# Un_Bus_B.net
KiCad netlist of a schematic drawn in EAGLE
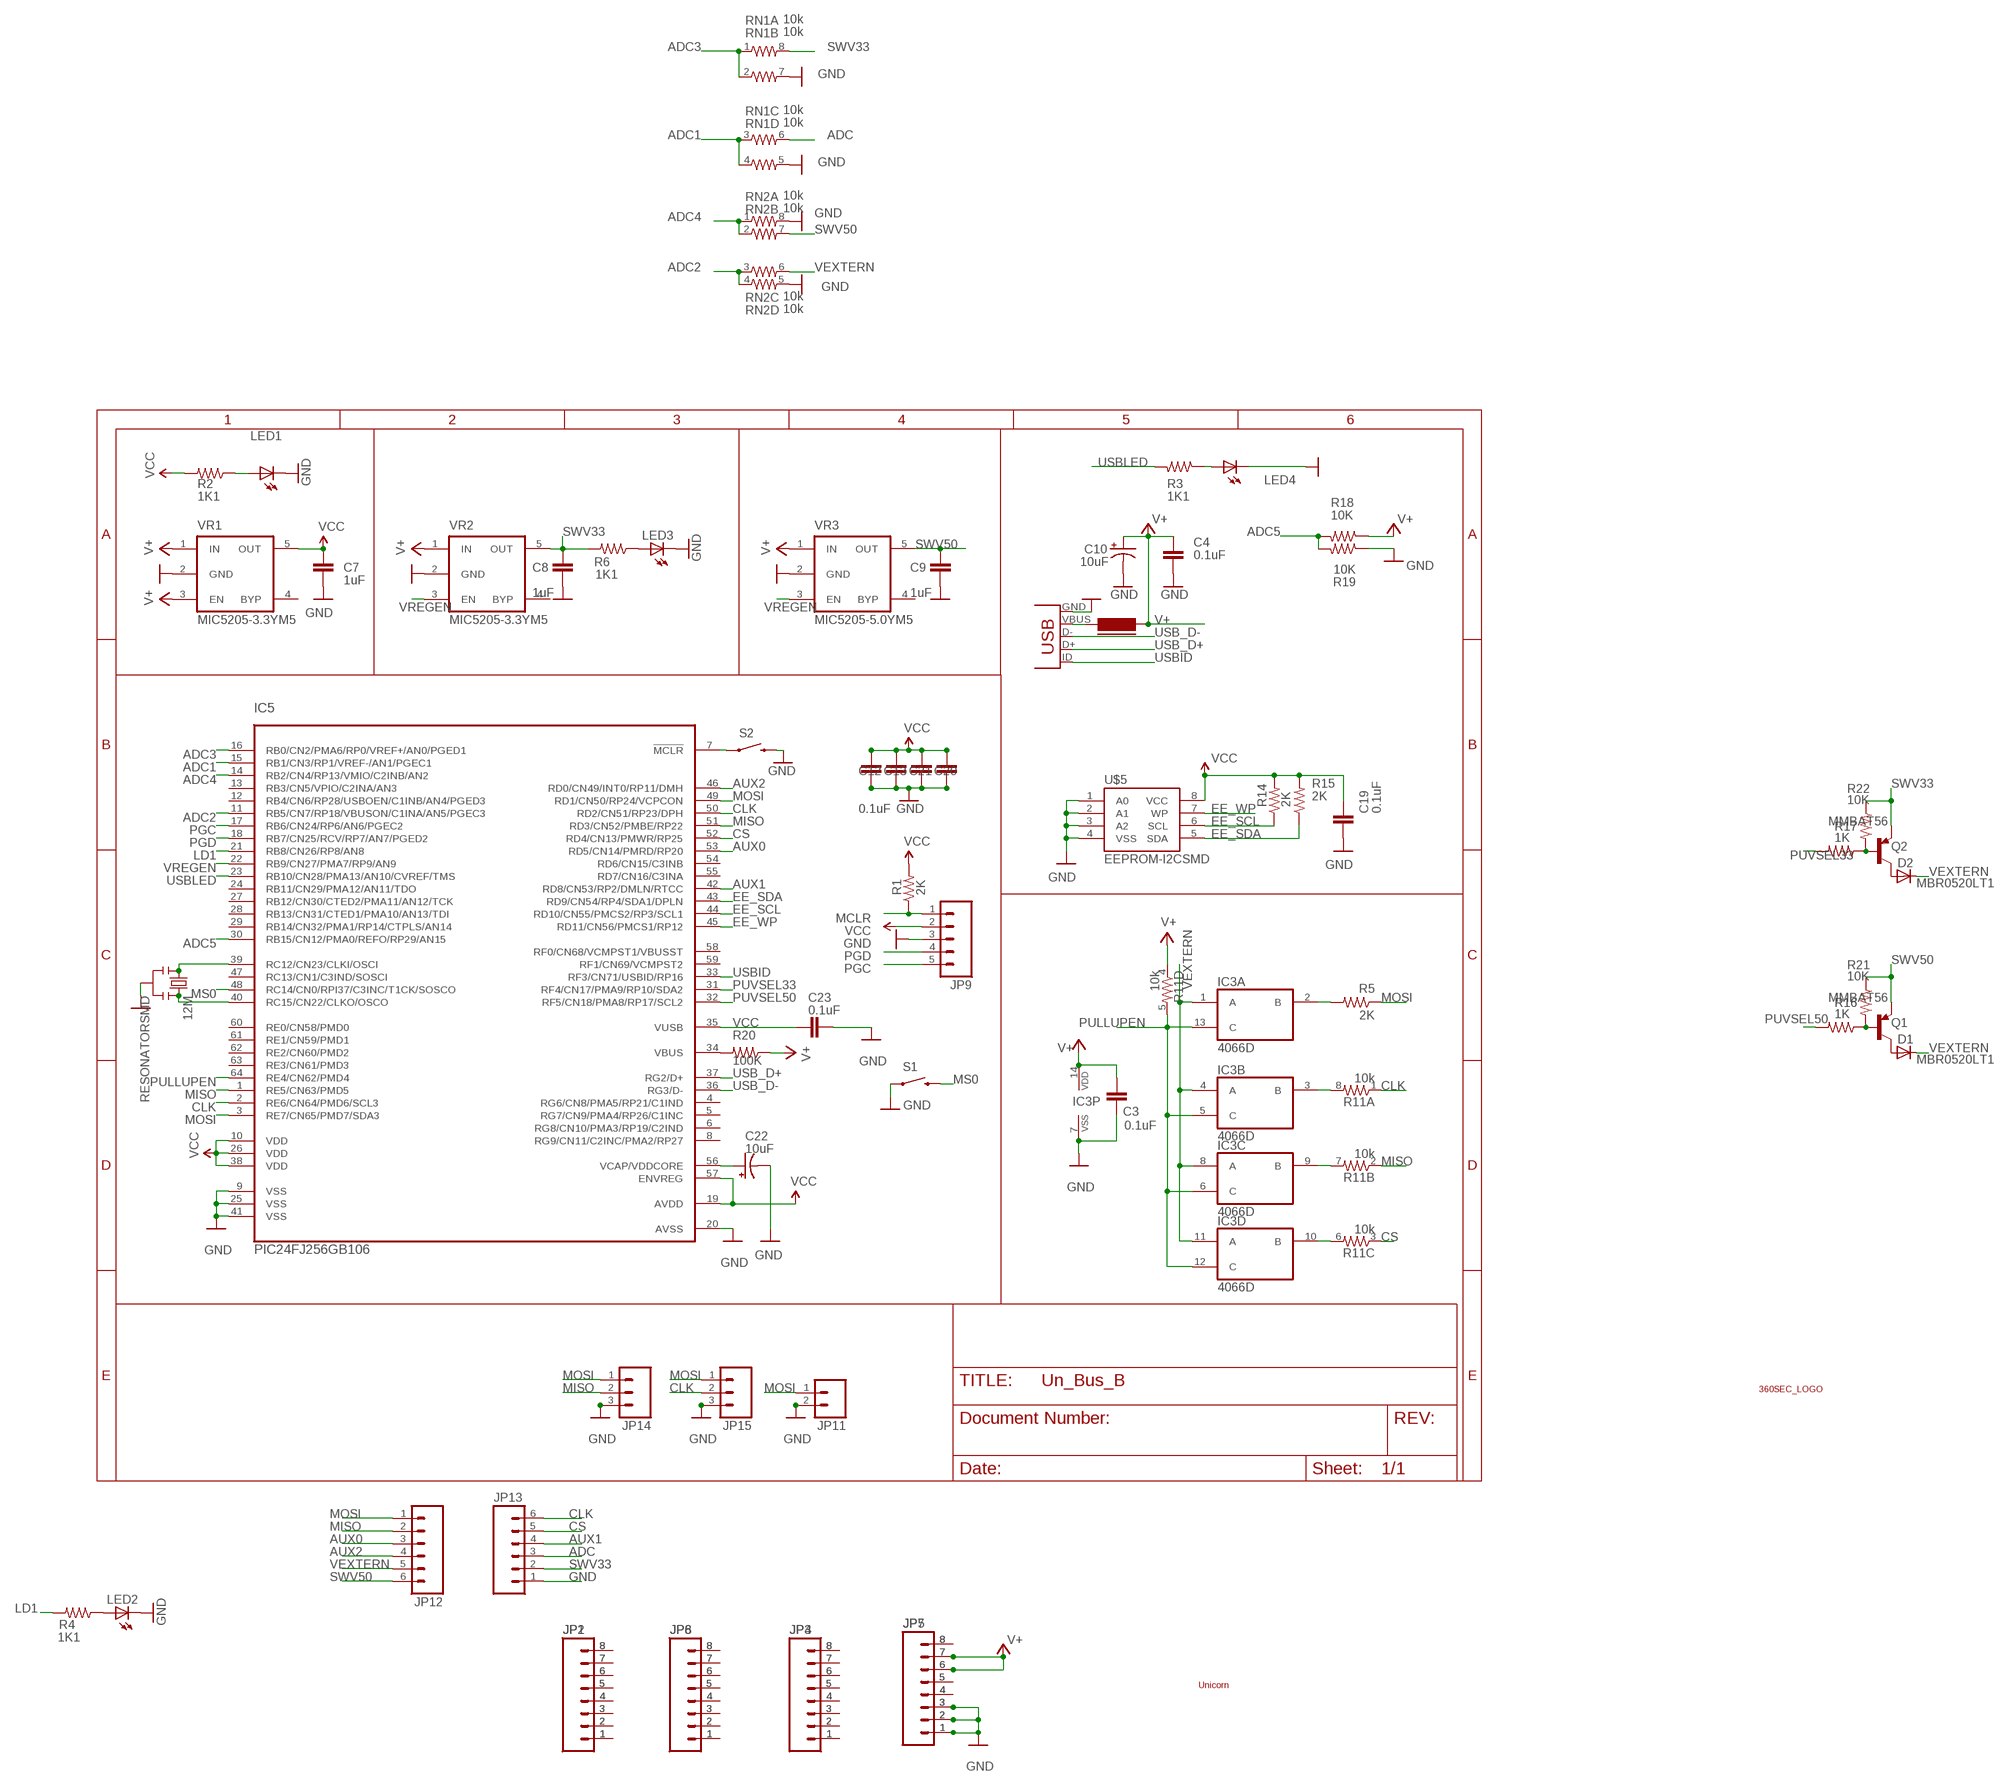
[diagram p0: schematic, sheet 1]

(export (version "E")
  (design (tool "Eeschema 10.0.6"))
  (components
    (comp (ref "12M")
      (value "RESONATORSMD")
      (footprint "eagle-import:RESONATOR-SMD")
      (libsource (lib "eagle-import") (part "RESONATORSMD"))
    )
    (comp (ref "C3")
      (value "0.1uF")
      (footprint "eagle-import:0603-CAP")
      (libsource (lib "eagle-import") (part "CAP0603-CAP"))
    )
    (comp (ref "C4")
      (value "0.1uF")
      (footprint "eagle-import:0603-CAP")
      (libsource (lib "eagle-import") (part "CAP0603-CAP"))
    )
    (comp (ref "C7")
      (value "1uF")
      (footprint "eagle-import:0603-CAP")
      (libsource (lib "eagle-import") (part "CAP0603-CAP"))
    )
    (comp (ref "C8")
      (value "1uF")
      (footprint "eagle-import:0603-CAP")
      (libsource (lib "eagle-import") (part "CAP0603-CAP"))
    )
    (comp (ref "C9")
      (value "1uF")
      (footprint "eagle-import:0603-CAP")
      (libsource (lib "eagle-import") (part "CAP0603-CAP"))
    )
    (comp (ref "C10")
      (value "10uF")
      (footprint "eagle-import:EIA3216")
      (libsource (lib "eagle-import") (part "CAP_POL1206"))
    )
    (comp (ref "C12")
      (value "0.1uF")
      (footprint "eagle-import:0603-CAP")
      (libsource (lib "eagle-import") (part "CAP0603-CAP"))
    )
    (comp (ref "C13")
      (value "0.1uF")
      (footprint "eagle-import:0603-CAP")
      (libsource (lib "eagle-import") (part "CAP0603-CAP"))
    )
    (comp (ref "C19")
      (value "0.1uF")
      (footprint "eagle-import:0603-CAP")
      (libsource (lib "eagle-import") (part "CAP0603-CAP"))
    )
    (comp (ref "C20")
      (value "0.1uF")
      (footprint "eagle-import:0603-CAP")
      (libsource (lib "eagle-import") (part "CAP0603-CAP"))
    )
    (comp (ref "C21")
      (value "0.1uF")
      (footprint "eagle-import:0603-CAP")
      (libsource (lib "eagle-import") (part "CAP0603-CAP"))
    )
    (comp (ref "C22")
      (value "10uF")
      (footprint "eagle-import:EIA3216")
      (libsource (lib "eagle-import") (part "CAP_POL1206"))
    )
    (comp (ref "C23")
      (value "0.1uF")
      (footprint "eagle-import:0603-CAP")
      (libsource (lib "eagle-import") (part "CAP0603-CAP"))
    )
    (comp (ref "D1")
      (value "MBR0520LT1")
      (footprint "eagle-import:SOD123")
      (libsource (lib "eagle-import") (part "MBR0520LT"))
    )
    (comp (ref "D2")
      (value "MBR0520LT1")
      (footprint "eagle-import:SOD123")
      (libsource (lib "eagle-import") (part "MBR0520LT"))
    )
    (comp (ref "IC3")
      (value "4066D")
      (footprint "eagle-import:SO14")
      (libsource (lib "eagle-import") (part "4066D"))
    )
    (comp (ref "IC5")
      (value "PIC24FJ256GB106")
      (footprint "eagle-import:TQFP64-10X10")
      (libsource (lib "eagle-import") (part "PIC24FJ256GB106"))
    )
    (comp (ref "JP1")
      (value "M081X08")
      (footprint "eagle-import:1X08")
      (libsource (lib "eagle-import") (part "M081X08"))
    )
    (comp (ref "JP2")
      (value "M081X08")
      (footprint "eagle-import:1X08")
      (libsource (lib "eagle-import") (part "M081X08"))
    )
    (comp (ref "JP3")
      (value "M081X08")
      (footprint "eagle-import:1X08")
      (libsource (lib "eagle-import") (part "M081X08"))
    )
    (comp (ref "JP4")
      (value "M081X08")
      (footprint "eagle-import:1X08")
      (libsource (lib "eagle-import") (part "M081X08"))
    )
    (comp (ref "JP5")
      (value "M081X08")
      (footprint "eagle-import:1X08")
      (libsource (lib "eagle-import") (part "M081X08"))
    )
    (comp (ref "JP6")
      (value "M081X08")
      (footprint "eagle-import:1X08")
      (libsource (lib "eagle-import") (part "M081X08"))
    )
    (comp (ref "JP7")
      (value "M081X08")
      (footprint "eagle-import:1X08")
      (libsource (lib "eagle-import") (part "M081X08"))
    )
    (comp (ref "JP8")
      (value "M081X08")
      (footprint "eagle-import:1X08")
      (libsource (lib "eagle-import") (part "M081X08"))
    )
    (comp (ref "JP9")
      (value "M05PTH")
      (footprint "eagle-import:1X05")
      (libsource (lib "eagle-import") (part "M05PTH"))
    )
    (comp (ref "JP11")
      (value "M02PTH")
      (footprint "eagle-import:1X02")
      (libsource (lib "eagle-import") (part "M02PTH"))
    )
    (comp (ref "JP12")
      (value "M06SIP")
      (footprint "eagle-import:1X06")
      (libsource (lib "eagle-import") (part "M06SIP"))
    )
    (comp (ref "JP13")
      (value "M06SIP")
      (footprint "eagle-import:1X06")
      (libsource (lib "eagle-import") (part "M06SIP"))
    )
    (comp (ref "JP14")
      (value "M03PTH")
      (footprint "eagle-import:1X03")
      (libsource (lib "eagle-import") (part "M03PTH"))
    )
    (comp (ref "JP15")
      (value "M03PTH")
      (footprint "eagle-import:1X03")
      (libsource (lib "eagle-import") (part "M03PTH"))
    )
    (comp (ref "L1")
      (value "700mA+ ferrite")
      (footprint "eagle-import:FB805")
      (libsource (lib "eagle-import") (part "FERRITE-0805"))
    )
    (comp (ref "LED1")
      (value "LED0805")
      (footprint "eagle-import:LED-0805")
      (libsource (lib "eagle-import") (part "LED0805"))
    )
    (comp (ref "LED2")
      (value "LED0805")
      (footprint "eagle-import:LED-0805")
      (libsource (lib "eagle-import") (part "LED0805"))
    )
    (comp (ref "LED3")
      (value "LED0805")
      (footprint "eagle-import:LED-0805")
      (libsource (lib "eagle-import") (part "LED0805"))
    )
    (comp (ref "LED4")
      (value "LED0805")
      (footprint "eagle-import:LED-0805")
      (libsource (lib "eagle-import") (part "LED0805"))
    )
    (comp (ref "Q1")
      (value "MMBAT56")
      (footprint "eagle-import:SOT23")
      (libsource (lib "eagle-import") (part "-?SOT23MMBTA56"))
    )
    (comp (ref "Q2")
      (value "MMBAT56")
      (footprint "eagle-import:SOT23")
      (libsource (lib "eagle-import") (part "-?SOT23MMBTA56"))
    )
    (comp (ref "R1")
      (value "2K")
      (footprint "eagle-import:0603-RES")
      (libsource (lib "eagle-import") (part "2SparkFun_RESISTOR0603-RES"))
    )
    (comp (ref "R2")
      (value "1K1")
      (footprint "eagle-import:0603-RES")
      (libsource (lib "eagle-import") (part "RESISTOR0603-RES"))
    )
    (comp (ref "R3")
      (value "1K1")
      (footprint "eagle-import:0603-RES")
      (libsource (lib "eagle-import") (part "RESISTOR0603-RES"))
    )
    (comp (ref "R4")
      (value "1K1")
      (footprint "eagle-import:0603-RES")
      (libsource (lib "eagle-import") (part "RESISTOR0603-RES"))
    )
    (comp (ref "R5")
      (value "2K")
      (footprint "eagle-import:0603-RES")
      (libsource (lib "eagle-import") (part "2SparkFun_RESISTOR0603-RES"))
    )
    (comp (ref "R6")
      (value "1K1")
      (footprint "eagle-import:0603-RES")
      (libsource (lib "eagle-import") (part "RESISTOR0603-RES"))
    )
    (comp (ref "R11")
      (value "10k")
      (footprint "eagle-import:RES-NET-0603")
      (libsource (lib "eagle-import") (part "RESISTOR-ARRAY"))
    )
    (comp (ref "R14")
      (value "2K")
      (footprint "eagle-import:0603-RES")
      (libsource (lib "eagle-import") (part "2SparkFun_RESISTOR0603-RES"))
    )
    (comp (ref "R15")
      (value "2K")
      (footprint "eagle-import:0603-RES")
      (libsource (lib "eagle-import") (part "2SparkFun_RESISTOR0603-RES"))
    )
    (comp (ref "R16")
      (value "1K")
      (footprint "eagle-import:0603-RES")
      (libsource (lib "eagle-import") (part "2SparkFun_RESISTOR0603-RES"))
    )
    (comp (ref "R17")
      (value "1K")
      (footprint "eagle-import:0603-RES")
      (libsource (lib "eagle-import") (part "2SparkFun_RESISTOR0603-RES"))
    )
    (comp (ref "R18")
      (value "10K")
      (footprint "eagle-import:0603-RES")
      (libsource (lib "eagle-import") (part "2SparkFun_RESISTOR0603-RES"))
    )
    (comp (ref "R19")
      (value "10K")
      (footprint "eagle-import:0603-RES")
      (libsource (lib "eagle-import") (part "2SparkFun_RESISTOR0603-RES"))
    )
    (comp (ref "R20")
      (value "100K")
      (footprint "eagle-import:0603-RES")
      (libsource (lib "eagle-import") (part "2SparkFun_RESISTOR0603-RES"))
    )
    (comp (ref "R21")
      (value "10K")
      (footprint "eagle-import:0603-RES")
      (libsource (lib "eagle-import") (part "2SparkFun_RESISTOR0603-RES"))
    )
    (comp (ref "R22")
      (value "10K")
      (footprint "eagle-import:0603-RES")
      (libsource (lib "eagle-import") (part "2SparkFun_RESISTOR0603-RES"))
    )
    (comp (ref "RN1")
      (value "10k")
      (footprint "eagle-import:RES-NET-0603")
      (libsource (lib "eagle-import") (part "RESISTOR-ARRAY"))
    )
    (comp (ref "RN2")
      (value "10k")
      (footprint "eagle-import:RES-NET-0603")
      (libsource (lib "eagle-import") (part "RESISTOR-ARRAY"))
    )
    (comp (ref "S1")
      (value "SWITCH-MOMENTARY-2-SMD-1101NE")
      (footprint "eagle-import:TACTILE-SWITCH-1101NE")
      (libsource (lib "eagle-import") (part "SWITCH-MOMENTARY-2-SMD-1101NE"))
    )
    (comp (ref "S2")
      (value "SWITCH-MOMENTARY-2-SMD-1101NE")
      (footprint "eagle-import:TACTILE-SWITCH-1101NE")
      (libsource (lib "eagle-import") (part "SWITCH-MOMENTARY-2-SMD-1101NE"))
    )
    (comp (ref "U$1")
      (value "UNICORN")
      (footprint "eagle-import:UNICORN_1")
      (libsource (lib "eagle-import") (part "UNICORN"))
    )
    (comp (ref "U$3")
      (value "360SEC_LOGO_1")
      (footprint "eagle-import:360SEC_1")
      (libsource (lib "eagle-import") (part "360SEC_LOGO_1"))
    )
    (comp (ref "U$5")
      (value "EEPROM-I2CSMD")
      (footprint "eagle-import:SO08")
      (libsource (lib "eagle-import") (part "EEPROM-I2CSMD"))
    )
    (comp (ref "VR1")
      (value "MIC5205-3.3YM5")
      (footprint "eagle-import:SOT-23-5")
      (libsource (lib "eagle-import") (part "MIC5205"))
    )
    (comp (ref "VR2")
      (value "MIC5205-3.3YM5")
      (footprint "eagle-import:SOT-23-5")
      (libsource (lib "eagle-import") (part "MIC5205"))
    )
    (comp (ref "VR3")
      (value "MIC5205-5.0YM5")
      (footprint "eagle-import:SOT-23-5")
      (libsource (lib "eagle-import") (part "MIC5205"))
    )
    (comp (ref "X1")
      (value "USBSMD")
      (footprint "eagle-import:USB-MINIB")
      (libsource (lib "eagle-import") (part "USBSMD"))
    )
  )
  (nets
    (net (code "1") (name "/ADC") (class "Default")
      (node (ref "JP13") (pin "3") (pinfunction "3_3") (pintype "passive"))
      (node (ref "RN1") (pin "6") (pinfunction "2_6") (pintype "passive"))
    )
    (net (code "2") (name "/ADC1") (class "Default")
      (node (ref "IC5") (pin "15") (pinfunction "RB1/CN3/RP1/VREF-/AN1/PGEC1_15") (pintype "bidirectional"))
      (node (ref "RN1") (pin "3") (pinfunction "1_3") (pintype "passive"))
      (node (ref "RN1") (pin "4") (pinfunction "1_4") (pintype "passive"))
    )
    (net (code "3") (name "/ADC2") (class "Default")
      (node (ref "IC5") (pin "11") (pinfunction "RB5/CN7/RP18/VBUSON/C1INA/AN5/PGEC3_11") (pintype "bidirectional"))
      (node (ref "RN2") (pin "3") (pinfunction "1_3") (pintype "passive"))
      (node (ref "RN2") (pin "4") (pinfunction "1_4") (pintype "passive"))
    )
    (net (code "4") (name "/ADC3") (class "Default")
      (node (ref "IC5") (pin "16") (pinfunction "RB0/CN2/PMA6/RP0/VREF+/AN0/PGED1_16") (pintype "bidirectional"))
      (node (ref "RN1") (pin "1") (pinfunction "1_1") (pintype "passive"))
      (node (ref "RN1") (pin "2") (pinfunction "1_2") (pintype "passive"))
    )
    (net (code "5") (name "/ADC4") (class "Default")
      (node (ref "IC5") (pin "14") (pinfunction "RB2/CN4/RP13/VMIO/C2INB/AN2_14") (pintype "bidirectional"))
      (node (ref "RN2") (pin "1") (pinfunction "1_1") (pintype "passive"))
      (node (ref "RN2") (pin "2") (pinfunction "1_2") (pintype "passive"))
    )
    (net (code "6") (name "/ADC5") (class "Default")
      (node (ref "IC5") (pin "30") (pinfunction "RB15/CN12/PMA0/REFO/RP29/AN15_30") (pintype "bidirectional"))
      (node (ref "R18") (pin "2") (pinfunction "2_2") (pintype "passive"))
      (node (ref "R19") (pin "2") (pinfunction "2_2") (pintype "passive"))
    )
    (net (code "7") (name "/AUX0") (class "Default")
      (node (ref "IC5") (pin "53") (pinfunction "RD5/CN14/PMRD/RP20_53") (pintype "bidirectional"))
      (node (ref "JP12") (pin "3") (pinfunction "3_3") (pintype "passive"))
    )
    (net (code "8") (name "/AUX1") (class "Default")
      (node (ref "IC5") (pin "42") (pinfunction "RD8/CN53/RP2/DMLN/RTCC_42") (pintype "bidirectional"))
      (node (ref "JP13") (pin "4") (pinfunction "4_4") (pintype "passive"))
    )
    (net (code "9") (name "/AUX2") (class "Default")
      (node (ref "IC5") (pin "46") (pinfunction "RD0/CN49/INT0/RP11/DMH_46") (pintype "bidirectional"))
      (node (ref "JP12") (pin "4") (pinfunction "4_4") (pintype "passive"))
    )
    (net (code "10") (name "/CLK") (class "Default")
      (node (ref "IC5") (pin "2") (pinfunction "RE6/CN64/PMD6/SCL3_2") (pintype "bidirectional"))
      (node (ref "IC5") (pin "50") (pinfunction "RD2/CN51/RP23/DPH_50") (pintype "bidirectional"))
      (node (ref "JP13") (pin "6") (pinfunction "6_6") (pintype "passive"))
      (node (ref "JP15") (pin "2") (pinfunction "2_2") (pintype "passive"))
      (node (ref "R11") (pin "1") (pinfunction "1_1") (pintype "passive"))
    )
    (net (code "11") (name "/CS") (class "Default")
      (node (ref "IC5") (pin "52") (pinfunction "RD4/CN13/PMWR/RP25_52") (pintype "bidirectional"))
      (node (ref "JP13") (pin "5") (pinfunction "5_5") (pintype "passive"))
      (node (ref "R11") (pin "3") (pinfunction "1_3") (pintype "passive"))
    )
    (net (code "12") (name "/EE_SCL") (class "Default")
      (node (ref "IC5") (pin "44") (pinfunction "RD10/CN55/PMCS2/RP3/SCL1_44") (pintype "bidirectional"))
      (node (ref "R14") (pin "1") (pinfunction "1_1") (pintype "passive"))
      (node (ref "U$5") (pin "6") (pinfunction "SCL_6") (pintype "bidirectional"))
    )
    (net (code "13") (name "/EE_SDA") (class "Default")
      (node (ref "IC5") (pin "43") (pinfunction "RD9/CN54/RP4/SDA1/DPLN_43") (pintype "bidirectional"))
      (node (ref "R15") (pin "1") (pinfunction "1_1") (pintype "passive"))
      (node (ref "U$5") (pin "5") (pinfunction "SDA_5") (pintype "bidirectional"))
    )
    (net (code "14") (name "/EE_WP") (class "Default")
      (node (ref "IC5") (pin "45") (pinfunction "RD11/CN56/PMCS1/RP12_45") (pintype "bidirectional"))
      (node (ref "U$5") (pin "7") (pinfunction "WP_7") (pintype "bidirectional"))
    )
    (net (code "15") (name "/LD1") (class "Default")
      (node (ref "IC5") (pin "21") (pinfunction "RB8/CN26/RP8/AN8_21") (pintype "bidirectional"))
      (node (ref "R4") (pin "2") (pinfunction "2_2") (pintype "passive"))
    )
    (net (code "16") (name "/MCLR") (class "Default")
      (node (ref "IC5") (pin "7") (pinfunction "~{MCLR}_7") (pintype "input"))
      (node (ref "JP9") (pin "1") (pinfunction "1_1") (pintype "passive"))
      (node (ref "R1") (pin "1") (pinfunction "1_1") (pintype "passive"))
      (node (ref "S2") (pin "P$1") (pinfunction "1_P$1") (pintype "passive"))
    )
    (net (code "17") (name "/MISO") (class "Default")
      (node (ref "IC5") (pin "1") (pinfunction "RE5/CN63/PMD5_1") (pintype "bidirectional"))
      (node (ref "IC5") (pin "51") (pinfunction "RD3/CN52/PMBE/RP22_51") (pintype "bidirectional"))
      (node (ref "JP12") (pin "2") (pinfunction "2_2") (pintype "passive"))
      (node (ref "JP14") (pin "2") (pinfunction "2_2") (pintype "passive"))
      (node (ref "R11") (pin "2") (pinfunction "1_2") (pintype "passive"))
    )
    (net (code "18") (name "/MOSI") (class "Default")
      (node (ref "IC5") (pin "3") (pinfunction "RE7/CN65/PMD7/SDA3_3") (pintype "bidirectional"))
      (node (ref "IC5") (pin "49") (pinfunction "RD1/CN50/RP24/VCPCON_49") (pintype "bidirectional"))
      (node (ref "JP11") (pin "1") (pinfunction "1_1") (pintype "passive"))
      (node (ref "JP12") (pin "1") (pinfunction "1_1") (pintype "passive"))
      (node (ref "JP14") (pin "1") (pinfunction "1_1") (pintype "passive"))
      (node (ref "JP15") (pin "1") (pinfunction "1_1") (pintype "passive"))
      (node (ref "R5") (pin "1") (pinfunction "1_1") (pintype "passive"))
    )
    (net (code "19") (name "/MS0") (class "Default")
      (node (ref "IC5") (pin "48") (pinfunction "RC14/CN0/RPI37/C3INC/T1CK/SOSCO_48") (pintype "bidirectional"))
      (node (ref "S1") (pin "P$2") (pinfunction "2_P$2") (pintype "passive"))
    )
    (net (code "20") (name "/PGC") (class "Default")
      (node (ref "IC5") (pin "17") (pinfunction "RB6/CN24/RP6/AN6/PGEC2_17") (pintype "bidirectional"))
      (node (ref "JP9") (pin "5") (pinfunction "5_5") (pintype "passive"))
    )
    (net (code "21") (name "/PGD") (class "Default")
      (node (ref "IC5") (pin "18") (pinfunction "RB7/CN25/RCV/RP7/AN7/PGED2_18") (pintype "bidirectional"))
      (node (ref "JP9") (pin "4") (pinfunction "4_4") (pintype "passive"))
    )
    (net (code "22") (name "/PULLUPEN") (class "Default")
      (node (ref "IC3") (pin "12") (pinfunction "C_12") (pintype "input"))
      (node (ref "IC3") (pin "13") (pinfunction "C_13") (pintype "input"))
      (node (ref "IC3") (pin "5") (pinfunction "C_5") (pintype "input"))
      (node (ref "IC3") (pin "6") (pinfunction "C_6") (pintype "input"))
      (node (ref "IC5") (pin "64") (pinfunction "RE4/CN62/PMD4_64") (pintype "bidirectional"))
      (node (ref "R11") (pin "5") (pinfunction "2_5") (pintype "passive"))
    )
    (net (code "23") (name "/PUVSEL33") (class "Default")
      (node (ref "IC5") (pin "31") (pinfunction "RF4/CN17/PMA9/RP10/SDA2_31") (pintype "bidirectional"))
      (node (ref "R17") (pin "2") (pinfunction "2_2") (pintype "passive"))
    )
    (net (code "24") (name "/PUVSEL50") (class "Default")
      (node (ref "IC5") (pin "32") (pinfunction "RF5/CN18/PMA8/RP17/SCL2_32") (pintype "bidirectional"))
      (node (ref "R16") (pin "2") (pinfunction "2_2") (pintype "passive"))
    )
    (net (code "25") (name "/SWV33") (class "Default")
      (node (ref "C8") (pin "1") (pinfunction "1_1") (pintype "passive"))
      (node (ref "JP13") (pin "2") (pinfunction "2_2") (pintype "passive"))
      (node (ref "Q2") (pin "2") (pinfunction "E_2") (pintype "passive"))
      (node (ref "R22") (pin "1") (pinfunction "1_1") (pintype "passive"))
      (node (ref "R6") (pin "2") (pinfunction "2_2") (pintype "passive"))
      (node (ref "RN1") (pin "8") (pinfunction "2_8") (pintype "passive"))
      (node (ref "VR2") (pin "5") (pinfunction "OUT_5") (pintype "bidirectional"))
    )
    (net (code "26") (name "/SWV50") (class "Default")
      (node (ref "C9") (pin "1") (pinfunction "1_1") (pintype "passive"))
      (node (ref "JP12") (pin "6") (pinfunction "6_6") (pintype "passive"))
      (node (ref "Q1") (pin "2") (pinfunction "E_2") (pintype "passive"))
      (node (ref "R21") (pin "1") (pinfunction "1_1") (pintype "passive"))
      (node (ref "RN2") (pin "7") (pinfunction "2_7") (pintype "passive"))
      (node (ref "VR3") (pin "5") (pinfunction "OUT_5") (pintype "bidirectional"))
    )
    (net (code "27") (name "/USBID") (class "Default")
      (node (ref "IC5") (pin "33") (pinfunction "RF3/CN71/USBID/RP16_33") (pintype "bidirectional"))
      (node (ref "X1") (pin "ID") (pinfunction "USBID_ID") (pintype "bidirectional"))
    )
    (net (code "28") (name "/USBLED") (class "Default")
      (node (ref "IC5") (pin "23") (pinfunction "RB10/CN28/PMA13/AN10/CVREF/TMS_23") (pintype "bidirectional"))
      (node (ref "R3") (pin "2") (pinfunction "2_2") (pintype "passive"))
    )
    (net (code "29") (name "/USB_D+") (class "Default")
      (node (ref "IC5") (pin "37") (pinfunction "RG2/D+_37") (pintype "bidirectional"))
      (node (ref "X1") (pin "D+") (pinfunction "D+_D+") (pintype "bidirectional"))
    )
    (net (code "30") (name "/USB_D-") (class "Default")
      (node (ref "IC5") (pin "36") (pinfunction "RG3/D-_36") (pintype "bidirectional"))
      (node (ref "X1") (pin "D-") (pinfunction "D-_D-") (pintype "bidirectional"))
    )
    (net (code "31") (name "/VEXTERN") (class "Default")
      (node (ref "D1") (pin "C") (pinfunction "C_C") (pintype "passive"))
      (node (ref "D2") (pin "C") (pinfunction "C_C") (pintype "passive"))
      (node (ref "IC3") (pin "1") (pinfunction "A_1") (pintype "tri_state"))
      (node (ref "IC3") (pin "11") (pinfunction "A_11") (pintype "tri_state"))
      (node (ref "IC3") (pin "4") (pinfunction "A_4") (pintype "tri_state"))
      (node (ref "IC3") (pin "8") (pinfunction "A_8") (pintype "tri_state"))
      (node (ref "JP12") (pin "5") (pinfunction "5_5") (pintype "passive"))
      (node (ref "RN2") (pin "6") (pinfunction "2_6") (pintype "passive"))
    )
    (net (code "32") (name "/VREGEN") (class "Default")
      (node (ref "IC5") (pin "22") (pinfunction "RB9/CN27/PMA7/RP9/AN9_22") (pintype "bidirectional"))
      (node (ref "VR2") (pin "3") (pinfunction "EN_3") (pintype "bidirectional"))
      (node (ref "VR3") (pin "3") (pinfunction "EN_3") (pintype "bidirectional"))
    )
    (net (code "33") (name "GND") (class "Default")
      (node (ref "12M") (pin "2") (pinfunction "2_2") (pintype "passive"))
      (node (ref "C10") (pin "C") (pinfunction "-_C") (pintype "passive"))
      (node (ref "C12") (pin "2") (pinfunction "2_2") (pintype "passive"))
      (node (ref "C13") (pin "2") (pinfunction "2_2") (pintype "passive"))
      (node (ref "C19") (pin "1") (pinfunction "1_1") (pintype "passive"))
      (node (ref "C20") (pin "2") (pinfunction "2_2") (pintype "passive"))
      (node (ref "C21") (pin "2") (pinfunction "2_2") (pintype "passive"))
      (node (ref "C22") (pin "C") (pinfunction "-_C") (pintype "passive"))
      (node (ref "C23") (pin "2") (pinfunction "2_2") (pintype "passive"))
      (node (ref "C3") (pin "2") (pinfunction "2_2") (pintype "passive"))
      (node (ref "C4") (pin "2") (pinfunction "2_2") (pintype "passive"))
      (node (ref "C7") (pin "2") (pinfunction "2_2") (pintype "passive"))
      (node (ref "C8") (pin "2") (pinfunction "2_2") (pintype "passive"))
      (node (ref "C9") (pin "2") (pinfunction "2_2") (pintype "passive"))
      (node (ref "IC3") (pin "7") (pinfunction "VSS_7") (pintype "power_in"))
      (node (ref "IC5") (pin "20") (pinfunction "AVSS_20") (pintype "power_in"))
      (node (ref "IC5") (pin "25") (pinfunction "VSS_25") (pintype "power_in"))
      (node (ref "IC5") (pin "41") (pinfunction "VSS_41") (pintype "power_in"))
      (node (ref "IC5") (pin "9") (pinfunction "VSS_9") (pintype "power_in"))
      (node (ref "JP11") (pin "2") (pinfunction "2_2") (pintype "passive"))
      (node (ref "JP13") (pin "1") (pinfunction "1_1") (pintype "passive"))
      (node (ref "JP14") (pin "3") (pinfunction "3_3") (pintype "passive"))
      (node (ref "JP15") (pin "3") (pinfunction "3_3") (pintype "passive"))
      (node (ref "JP5") (pin "1") (pinfunction "1_1") (pintype "passive"))
      (node (ref "JP5") (pin "2") (pinfunction "2_2") (pintype "passive"))
      (node (ref "JP5") (pin "3") (pinfunction "3_3") (pintype "passive"))
      (node (ref "JP7") (pin "1") (pinfunction "1_1") (pintype "passive"))
      (node (ref "JP7") (pin "2") (pinfunction "2_2") (pintype "passive"))
      (node (ref "JP7") (pin "3") (pinfunction "3_3") (pintype "passive"))
      (node (ref "JP9") (pin "3") (pinfunction "3_3") (pintype "passive"))
      (node (ref "LED1") (pin "2") (pinfunction "C_2") (pintype "passive"))
      (node (ref "LED2") (pin "2") (pinfunction "C_2") (pintype "passive"))
      (node (ref "LED3") (pin "2") (pinfunction "C_2") (pintype "passive"))
      (node (ref "LED4") (pin "2") (pinfunction "C_2") (pintype "passive"))
      (node (ref "R19") (pin "1") (pinfunction "1_1") (pintype "passive"))
      (node (ref "RN1") (pin "5") (pinfunction "2_5") (pintype "passive"))
      (node (ref "RN1") (pin "7") (pinfunction "2_7") (pintype "passive"))
      (node (ref "RN2") (pin "5") (pinfunction "2_5") (pintype "passive"))
      (node (ref "RN2") (pin "8") (pinfunction "2_8") (pintype "passive"))
      (node (ref "S1") (pin "P$1") (pinfunction "1_P$1") (pintype "passive"))
      (node (ref "S2") (pin "P$2") (pinfunction "2_P$2") (pintype "passive"))
      (node (ref "U$5") (pin "1") (pinfunction "A0_1") (pintype "bidirectional"))
      (node (ref "U$5") (pin "2") (pinfunction "A1_2") (pintype "bidirectional"))
      (node (ref "U$5") (pin "3") (pinfunction "A2_3") (pintype "bidirectional"))
      (node (ref "U$5") (pin "4") (pinfunction "VSS_4") (pintype "power_in"))
      (node (ref "VR1") (pin "2") (pinfunction "GND_2") (pintype "bidirectional"))
      (node (ref "VR2") (pin "2") (pinfunction "GND_2") (pintype "bidirectional"))
      (node (ref "VR3") (pin "2") (pinfunction "GND_2") (pintype "bidirectional"))
      (node (ref "X1") (pin "GND") (pinfunction "GND_GND") (pintype "bidirectional"))
    )
    (net (code "34") (name "Net-(C22-+)") (class "Default")
      (node (ref "C22") (pin "A") (pinfunction "+_A") (pintype "passive"))
      (node (ref "IC5") (pin "56") (pinfunction "VCAP/VDDCORE_56") (pintype "bidirectional"))
    )
    (net (code "35") (name "Net-(IC3A-B)") (class "Default")
      (node (ref "IC3") (pin "2") (pinfunction "B_2") (pintype "tri_state"))
      (node (ref "R5") (pin "2") (pinfunction "2_2") (pintype "passive"))
    )
    (net (code "36") (name "Net-(IC3B-B)") (class "Default")
      (node (ref "IC3") (pin "3") (pinfunction "B_3") (pintype "tri_state"))
      (node (ref "R11") (pin "8") (pinfunction "2_8") (pintype "passive"))
    )
    (net (code "37") (name "Net-(IC3C-B)") (class "Default")
      (node (ref "IC3") (pin "9") (pinfunction "B_9") (pintype "tri_state"))
      (node (ref "R11") (pin "7") (pinfunction "2_7") (pintype "passive"))
    )
    (net (code "38") (name "Net-(IC3D-B)") (class "Default")
      (node (ref "IC3") (pin "10") (pinfunction "B_10") (pintype "tri_state"))
      (node (ref "R11") (pin "6") (pinfunction "2_6") (pintype "passive"))
    )
    (net (code "39") (name "Net-(IC5-RC12{slash}CN23{slash}CLKI{slash}OSCI)") (class "Default")
      (node (ref "12M") (pin "1") (pinfunction "1_1") (pintype "passive"))
      (node (ref "IC5") (pin "39") (pinfunction "RC12/CN23/CLKI/OSCI_39") (pintype "bidirectional"))
    )
    (net (code "40") (name "Net-(IC5-RC15{slash}CN22{slash}CLKO{slash}OSCO)") (class "Default")
      (node (ref "12M") (pin "3") (pinfunction "3_3") (pintype "passive"))
      (node (ref "IC5") (pin "40") (pinfunction "RC15/CN22/CLKO/OSCO_40") (pintype "bidirectional"))
    )
    (net (code "41") (name "Net-(IC5-VBUS)") (class "Default")
      (node (ref "IC5") (pin "34") (pinfunction "VBUS_34") (pintype "bidirectional"))
      (node (ref "R20") (pin "2") (pinfunction "2_2") (pintype "passive"))
    )
    (net (code "42") (name "Net-(JP1-Pad1)") (class "Default")
      (node (ref "JP1") (pin "1") (pinfunction "1_1") (pintype "passive"))
      (node (ref "JP2") (pin "1") (pinfunction "1_1") (pintype "passive"))
    )
    (net (code "43") (name "Net-(JP1-Pad2)") (class "Default")
      (node (ref "JP1") (pin "2") (pinfunction "2_2") (pintype "passive"))
      (node (ref "JP2") (pin "2") (pinfunction "2_2") (pintype "passive"))
    )
    (net (code "44") (name "Net-(JP1-Pad3)") (class "Default")
      (node (ref "JP1") (pin "3") (pinfunction "3_3") (pintype "passive"))
      (node (ref "JP2") (pin "3") (pinfunction "3_3") (pintype "passive"))
    )
    (net (code "45") (name "Net-(JP1-Pad4)") (class "Default")
      (node (ref "JP1") (pin "4") (pinfunction "4_4") (pintype "passive"))
      (node (ref "JP2") (pin "4") (pinfunction "4_4") (pintype "passive"))
    )
    (net (code "46") (name "Net-(JP1-Pad5)") (class "Default")
      (node (ref "JP1") (pin "5") (pinfunction "5_5") (pintype "passive"))
      (node (ref "JP2") (pin "5") (pinfunction "5_5") (pintype "passive"))
    )
    (net (code "47") (name "Net-(JP1-Pad6)") (class "Default")
      (node (ref "JP1") (pin "6") (pinfunction "6_6") (pintype "passive"))
      (node (ref "JP2") (pin "6") (pinfunction "6_6") (pintype "passive"))
    )
    (net (code "48") (name "Net-(JP1-Pad7)") (class "Default")
      (node (ref "JP1") (pin "7") (pinfunction "7_7") (pintype "passive"))
      (node (ref "JP2") (pin "7") (pinfunction "7_7") (pintype "passive"))
    )
    (net (code "49") (name "Net-(JP1-Pad8)") (class "Default")
      (node (ref "JP1") (pin "8") (pinfunction "8_8") (pintype "passive"))
      (node (ref "JP2") (pin "8") (pinfunction "8_8") (pintype "passive"))
    )
    (net (code "50") (name "Net-(JP3-Pad1)") (class "Default")
      (node (ref "JP3") (pin "1") (pinfunction "1_1") (pintype "passive"))
      (node (ref "JP4") (pin "1") (pinfunction "1_1") (pintype "passive"))
    )
    (net (code "51") (name "Net-(JP3-Pad2)") (class "Default")
      (node (ref "JP3") (pin "2") (pinfunction "2_2") (pintype "passive"))
      (node (ref "JP4") (pin "2") (pinfunction "2_2") (pintype "passive"))
    )
    (net (code "52") (name "Net-(JP3-Pad3)") (class "Default")
      (node (ref "JP3") (pin "3") (pinfunction "3_3") (pintype "passive"))
      (node (ref "JP4") (pin "3") (pinfunction "3_3") (pintype "passive"))
    )
    (net (code "53") (name "Net-(JP3-Pad4)") (class "Default")
      (node (ref "JP3") (pin "4") (pinfunction "4_4") (pintype "passive"))
      (node (ref "JP4") (pin "4") (pinfunction "4_4") (pintype "passive"))
    )
    (net (code "54") (name "Net-(JP3-Pad5)") (class "Default")
      (node (ref "JP3") (pin "5") (pinfunction "5_5") (pintype "passive"))
      (node (ref "JP4") (pin "5") (pinfunction "5_5") (pintype "passive"))
    )
    (net (code "55") (name "Net-(JP3-Pad6)") (class "Default")
      (node (ref "JP3") (pin "6") (pinfunction "6_6") (pintype "passive"))
      (node (ref "JP4") (pin "6") (pinfunction "6_6") (pintype "passive"))
    )
    (net (code "56") (name "Net-(JP3-Pad7)") (class "Default")
      (node (ref "JP3") (pin "7") (pinfunction "7_7") (pintype "passive"))
      (node (ref "JP4") (pin "7") (pinfunction "7_7") (pintype "passive"))
    )
    (net (code "57") (name "Net-(JP3-Pad8)") (class "Default")
      (node (ref "JP3") (pin "8") (pinfunction "8_8") (pintype "passive"))
      (node (ref "JP4") (pin "8") (pinfunction "8_8") (pintype "passive"))
    )
    (net (code "58") (name "Net-(JP5-Pad4)") (class "Default")
      (node (ref "JP5") (pin "4") (pinfunction "4_4") (pintype "passive"))
      (node (ref "JP7") (pin "4") (pinfunction "4_4") (pintype "passive"))
    )
    (net (code "59") (name "Net-(JP5-Pad5)") (class "Default")
      (node (ref "JP5") (pin "5") (pinfunction "5_5") (pintype "passive"))
      (node (ref "JP7") (pin "5") (pinfunction "5_5") (pintype "passive"))
    )
    (net (code "60") (name "Net-(JP5-Pad8)") (class "Default")
      (node (ref "JP5") (pin "8") (pinfunction "8_8") (pintype "passive"))
      (node (ref "JP7") (pin "8") (pinfunction "8_8") (pintype "passive"))
    )
    (net (code "61") (name "Net-(JP6-Pad1)") (class "Default")
      (node (ref "JP6") (pin "1") (pinfunction "1_1") (pintype "passive"))
      (node (ref "JP8") (pin "1") (pinfunction "1_1") (pintype "passive"))
    )
    (net (code "62") (name "Net-(JP6-Pad2)") (class "Default")
      (node (ref "JP6") (pin "2") (pinfunction "2_2") (pintype "passive"))
      (node (ref "JP8") (pin "2") (pinfunction "2_2") (pintype "passive"))
    )
    (net (code "63") (name "Net-(JP6-Pad3)") (class "Default")
      (node (ref "JP6") (pin "3") (pinfunction "3_3") (pintype "passive"))
      (node (ref "JP8") (pin "3") (pinfunction "3_3") (pintype "passive"))
    )
    (net (code "64") (name "Net-(JP6-Pad4)") (class "Default")
      (node (ref "JP6") (pin "4") (pinfunction "4_4") (pintype "passive"))
      (node (ref "JP8") (pin "4") (pinfunction "4_4") (pintype "passive"))
    )
    (net (code "65") (name "Net-(JP6-Pad5)") (class "Default")
      (node (ref "JP6") (pin "5") (pinfunction "5_5") (pintype "passive"))
      (node (ref "JP8") (pin "5") (pinfunction "5_5") (pintype "passive"))
    )
    (net (code "66") (name "Net-(JP6-Pad6)") (class "Default")
      (node (ref "JP6") (pin "6") (pinfunction "6_6") (pintype "passive"))
      (node (ref "JP8") (pin "6") (pinfunction "6_6") (pintype "passive"))
    )
    (net (code "67") (name "Net-(JP6-Pad7)") (class "Default")
      (node (ref "JP6") (pin "7") (pinfunction "7_7") (pintype "passive"))
      (node (ref "JP8") (pin "7") (pinfunction "7_7") (pintype "passive"))
    )
    (net (code "68") (name "Net-(JP6-Pad8)") (class "Default")
      (node (ref "JP6") (pin "8") (pinfunction "8_8") (pintype "passive"))
      (node (ref "JP8") (pin "8") (pinfunction "8_8") (pintype "passive"))
    )
    (net (code "69") (name "Net-(L1-Pad1)") (class "Default")
      (node (ref "L1") (pin "1") (pinfunction "1_1") (pintype "passive"))
      (node (ref "X1") (pin "VBUS") (pinfunction "VBUS_VBUS") (pintype "bidirectional"))
    )
    (net (code "70") (name "Net-(LED1-A)") (class "Default")
      (node (ref "LED1") (pin "1") (pinfunction "A_1") (pintype "passive"))
      (node (ref "R2") (pin "1") (pinfunction "1_1") (pintype "passive"))
    )
    (net (code "71") (name "Net-(LED2-A)") (class "Default")
      (node (ref "LED2") (pin "1") (pinfunction "A_1") (pintype "passive"))
      (node (ref "R4") (pin "1") (pinfunction "1_1") (pintype "passive"))
    )
    (net (code "72") (name "Net-(LED3-A)") (class "Default")
      (node (ref "LED3") (pin "1") (pinfunction "A_1") (pintype "passive"))
      (node (ref "R6") (pin "1") (pinfunction "1_1") (pintype "passive"))
    )
    (net (code "73") (name "Net-(LED4-A)") (class "Default")
      (node (ref "LED4") (pin "1") (pinfunction "A_1") (pintype "passive"))
      (node (ref "R3") (pin "1") (pinfunction "1_1") (pintype "passive"))
    )
    (net (code "74") (name "Net-(Q1-B)") (class "Default")
      (node (ref "Q1") (pin "1") (pinfunction "B_1") (pintype "passive"))
      (node (ref "R16") (pin "1") (pinfunction "1_1") (pintype "passive"))
      (node (ref "R21") (pin "2") (pinfunction "2_2") (pintype "passive"))
    )
    (net (code "75") (name "Net-(Q1-C)") (class "Default")
      (node (ref "D1") (pin "A") (pinfunction "A_A") (pintype "passive"))
      (node (ref "Q1") (pin "3") (pinfunction "C_3") (pintype "passive"))
    )
    (net (code "76") (name "Net-(Q2-B)") (class "Default")
      (node (ref "Q2") (pin "1") (pinfunction "B_1") (pintype "passive"))
      (node (ref "R17") (pin "1") (pinfunction "1_1") (pintype "passive"))
      (node (ref "R22") (pin "2") (pinfunction "2_2") (pintype "passive"))
    )
    (net (code "77") (name "Net-(Q2-C)") (class "Default")
      (node (ref "D2") (pin "A") (pinfunction "A_A") (pintype "passive"))
      (node (ref "Q2") (pin "3") (pinfunction "C_3") (pintype "passive"))
    )
    (net (code "78") (name "V+") (class "Default")
      (node (ref "C10") (pin "A") (pinfunction "+_A") (pintype "passive"))
      (node (ref "C3") (pin "1") (pinfunction "1_1") (pintype "passive"))
      (node (ref "C4") (pin "1") (pinfunction "1_1") (pintype "passive"))
      (node (ref "IC3") (pin "14") (pinfunction "VDD_14") (pintype "power_in"))
      (node (ref "JP5") (pin "6") (pinfunction "6_6") (pintype "passive"))
      (node (ref "JP5") (pin "7") (pinfunction "7_7") (pintype "passive"))
      (node (ref "JP7") (pin "6") (pinfunction "6_6") (pintype "passive"))
      (node (ref "JP7") (pin "7") (pinfunction "7_7") (pintype "passive"))
      (node (ref "L1") (pin "2") (pinfunction "2_2") (pintype "passive"))
      (node (ref "R11") (pin "4") (pinfunction "1_4") (pintype "passive"))
      (node (ref "R18") (pin "1") (pinfunction "1_1") (pintype "passive"))
      (node (ref "R20") (pin "1") (pinfunction "1_1") (pintype "passive"))
      (node (ref "VR1") (pin "1") (pinfunction "IN_1") (pintype "bidirectional"))
      (node (ref "VR1") (pin "3") (pinfunction "EN_3") (pintype "bidirectional"))
      (node (ref "VR2") (pin "1") (pinfunction "IN_1") (pintype "bidirectional"))
      (node (ref "VR3") (pin "1") (pinfunction "IN_1") (pintype "bidirectional"))
    )
    (net (code "79") (name "VCC") (class "Default")
      (node (ref "C12") (pin "1") (pinfunction "1_1") (pintype "passive"))
      (node (ref "C13") (pin "1") (pinfunction "1_1") (pintype "passive"))
      (node (ref "C19") (pin "2") (pinfunction "2_2") (pintype "passive"))
      (node (ref "C20") (pin "1") (pinfunction "1_1") (pintype "passive"))
      (node (ref "C21") (pin "1") (pinfunction "1_1") (pintype "passive"))
      (node (ref "C23") (pin "1") (pinfunction "1_1") (pintype "passive"))
      (node (ref "C7") (pin "1") (pinfunction "1_1") (pintype "passive"))
      (node (ref "IC5") (pin "10") (pinfunction "VDD_10") (pintype "power_in"))
      (node (ref "IC5") (pin "19") (pinfunction "AVDD_19") (pintype "power_in"))
      (node (ref "IC5") (pin "26") (pinfunction "VDD_26") (pintype "power_in"))
      (node (ref "IC5") (pin "35") (pinfunction "VUSB_35") (pintype "bidirectional"))
      (node (ref "IC5") (pin "38") (pinfunction "VDD_38") (pintype "power_in"))
      (node (ref "IC5") (pin "57") (pinfunction "ENVREG_57") (pintype "bidirectional"))
      (node (ref "JP9") (pin "2") (pinfunction "2_2") (pintype "passive"))
      (node (ref "R1") (pin "2") (pinfunction "2_2") (pintype "passive"))
      (node (ref "R14") (pin "2") (pinfunction "2_2") (pintype "passive"))
      (node (ref "R15") (pin "2") (pinfunction "2_2") (pintype "passive"))
      (node (ref "R2") (pin "2") (pinfunction "2_2") (pintype "passive"))
      (node (ref "U$5") (pin "8") (pinfunction "VCC_8") (pintype "power_in"))
      (node (ref "VR1") (pin "5") (pinfunction "OUT_5") (pintype "bidirectional"))
    )
    (net (code "80") (name "unconnected-(IC5-RB3{slash}CN5{slash}VPIO{slash}C2INA{slash}AN3-Pad13)") (class "Default")
      (node (ref "IC5") (pin "13") (pinfunction "RB3/CN5/VPIO/C2INA/AN3_13") (pintype "bidirectional"))
    )
    (net (code "81") (name "unconnected-(IC5-RB4{slash}CN6{slash}RP28{slash}USBOEN{slash}C1INB{slash}AN4{slash}PGED3-Pad12)") (class "Default")
      (node (ref "IC5") (pin "12") (pinfunction "RB4/CN6/RP28/USBOEN/C1INB/AN4/PGED3_12") (pintype "bidirectional"))
    )
    (net (code "82") (name "unconnected-(IC5-RB11{slash}CN29{slash}PMA12{slash}AN11{slash}TDO-Pad24)") (class "Default")
      (node (ref "IC5") (pin "24") (pinfunction "RB11/CN29/PMA12/AN11/TDO_24") (pintype "bidirectional"))
    )
    (net (code "83") (name "unconnected-(IC5-RB12{slash}CN30{slash}CTED2{slash}PMA11{slash}AN12{slash}TCK-Pad27)") (class "Default")
      (node (ref "IC5") (pin "27") (pinfunction "RB12/CN30/CTED2/PMA11/AN12/TCK_27") (pintype "bidirectional"))
    )
    (net (code "84") (name "unconnected-(IC5-RB13{slash}CN31{slash}CTED1{slash}PMA10{slash}AN13{slash}TDI-Pad28)") (class "Default")
      (node (ref "IC5") (pin "28") (pinfunction "RB13/CN31/CTED1/PMA10/AN13/TDI_28") (pintype "bidirectional"))
    )
    (net (code "85") (name "unconnected-(IC5-RB14{slash}CN32{slash}PMA1{slash}RP14{slash}CTPLS{slash}AN14-Pad29)") (class "Default")
      (node (ref "IC5") (pin "29") (pinfunction "RB14/CN32/PMA1/RP14/CTPLS/AN14_29") (pintype "bidirectional"))
    )
    (net (code "86") (name "unconnected-(IC5-RC13{slash}CN1{slash}C3IND{slash}SOSCI-Pad47)") (class "Default")
      (node (ref "IC5") (pin "47") (pinfunction "RC13/CN1/C3IND/SOSCI_47") (pintype "bidirectional"))
    )
    (net (code "87") (name "unconnected-(IC5-RD6{slash}CN15{slash}C3INB-Pad54)") (class "Default")
      (node (ref "IC5") (pin "54") (pinfunction "RD6/CN15/C3INB_54") (pintype "bidirectional"))
    )
    (net (code "88") (name "unconnected-(IC5-RD7{slash}CN16{slash}C3INA-Pad55)") (class "Default")
      (node (ref "IC5") (pin "55") (pinfunction "RD7/CN16/C3INA_55") (pintype "bidirectional"))
    )
    (net (code "89") (name "unconnected-(IC5-RE0{slash}CN58{slash}PMD0-Pad60)") (class "Default")
      (node (ref "IC5") (pin "60") (pinfunction "RE0/CN58/PMD0_60") (pintype "bidirectional"))
    )
    (net (code "90") (name "unconnected-(IC5-RE1{slash}CN59{slash}PMD1-Pad61)") (class "Default")
      (node (ref "IC5") (pin "61") (pinfunction "RE1/CN59/PMD1_61") (pintype "bidirectional"))
    )
    (net (code "91") (name "unconnected-(IC5-RE2{slash}CN60{slash}PMD2-Pad62)") (class "Default")
      (node (ref "IC5") (pin "62") (pinfunction "RE2/CN60/PMD2_62") (pintype "bidirectional"))
    )
    (net (code "92") (name "unconnected-(IC5-RE3{slash}CN61{slash}PMD3-Pad63)") (class "Default")
      (node (ref "IC5") (pin "63") (pinfunction "RE3/CN61/PMD3_63") (pintype "bidirectional"))
    )
    (net (code "93") (name "unconnected-(IC5-RF0{slash}CN68{slash}VCMPST1{slash}VBUSST-Pad58)") (class "Default")
      (node (ref "IC5") (pin "58") (pinfunction "RF0/CN68/VCMPST1/VBUSST_58") (pintype "bidirectional"))
    )
    (net (code "94") (name "unconnected-(IC5-RF1{slash}CN69{slash}VCMPST2-Pad59)") (class "Default")
      (node (ref "IC5") (pin "59") (pinfunction "RF1/CN69/VCMPST2_59") (pintype "bidirectional"))
    )
    (net (code "95") (name "unconnected-(IC5-RG6{slash}CN8{slash}PMA5{slash}RP21{slash}C1IND-Pad4)") (class "Default")
      (node (ref "IC5") (pin "4") (pinfunction "RG6/CN8/PMA5/RP21/C1IND_4") (pintype "bidirectional"))
    )
    (net (code "96") (name "unconnected-(IC5-RG7{slash}CN9{slash}PMA4{slash}RP26{slash}C1INC-Pad5)") (class "Default")
      (node (ref "IC5") (pin "5") (pinfunction "RG7/CN9/PMA4/RP26/C1INC_5") (pintype "bidirectional"))
    )
    (net (code "97") (name "unconnected-(IC5-RG8{slash}CN10{slash}PMA3{slash}RP19{slash}C2IND-Pad6)") (class "Default")
      (node (ref "IC5") (pin "6") (pinfunction "RG8/CN10/PMA3/RP19/C2IND_6") (pintype "bidirectional"))
    )
    (net (code "98") (name "unconnected-(IC5-RG9{slash}CN11{slash}C2INC{slash}PMA2{slash}RP27-Pad8)") (class "Default")
      (node (ref "IC5") (pin "8") (pinfunction "RG9/CN11/C2INC/PMA2/RP27_8") (pintype "bidirectional"))
    )
    (net (code "99") (name "unconnected-(VR1-BYP-Pad4)") (class "Default")
      (node (ref "VR1") (pin "4") (pinfunction "BYP_4") (pintype "bidirectional"))
    )
    (net (code "100") (name "unconnected-(VR2-BYP-Pad4)") (class "Default")
      (node (ref "VR2") (pin "4") (pinfunction "BYP_4") (pintype "bidirectional"))
    )
    (net (code "101") (name "unconnected-(VR3-BYP-Pad4)") (class "Default")
      (node (ref "VR3") (pin "4") (pinfunction "BYP_4") (pintype "bidirectional"))
    )
  )
)
